# LED_Leg.net
KiCad netlist of a schematic drawn in EAGLE
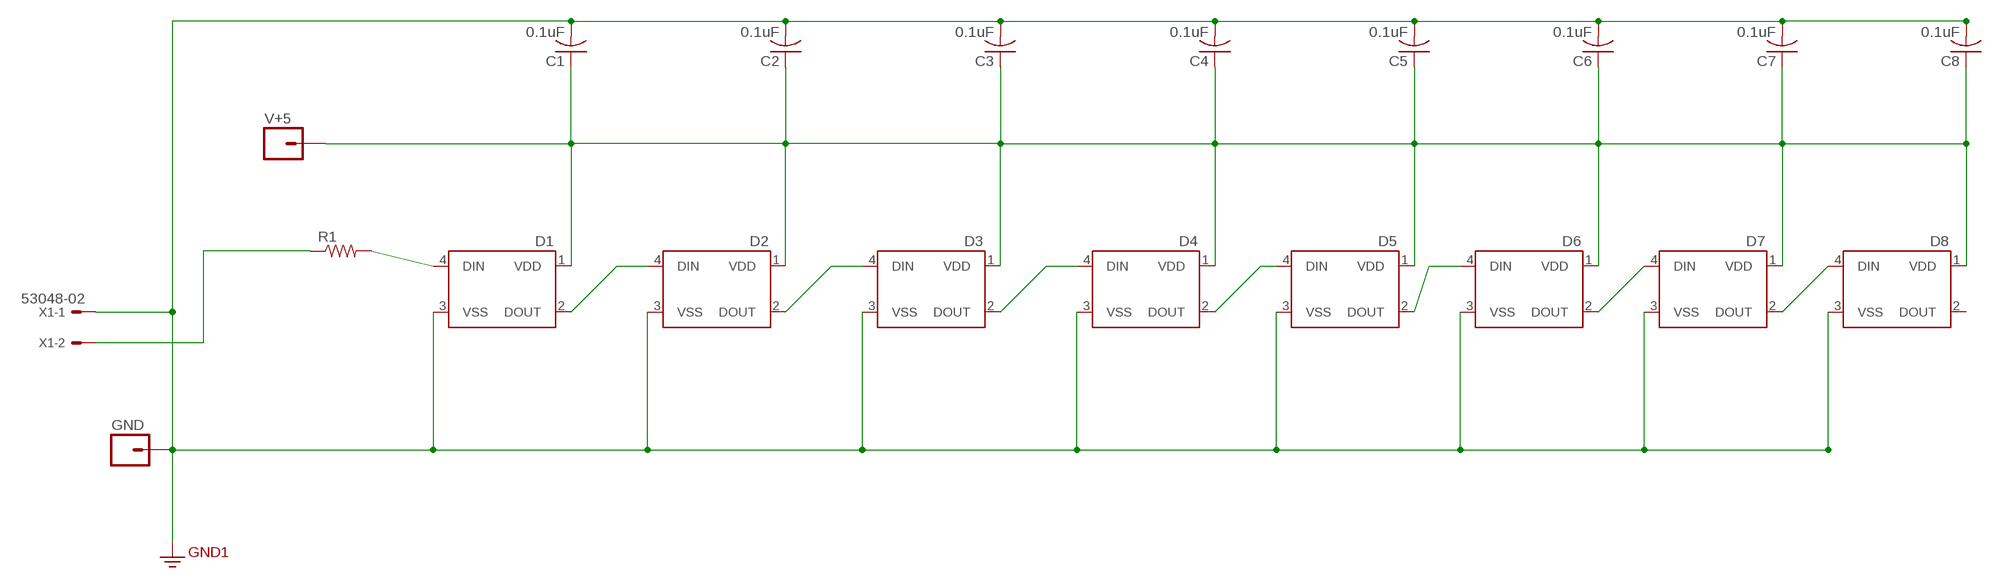
[diagram p0: schematic, sheet 1]

(export (version "E")
  (design (tool "Eeschema 10.0.6"))
  (components
    (comp (ref "C1")
      (value "0.1uF")
      (footprint "eagle-import:C0603K")
      (libsource (lib "eagle-import") (part "C-USC0603K"))
    )
    (comp (ref "C2")
      (value "0.1uF")
      (footprint "eagle-import:C0603K")
      (libsource (lib "eagle-import") (part "C-USC0603K"))
    )
    (comp (ref "C3")
      (value "0.1uF")
      (footprint "eagle-import:C0603K")
      (libsource (lib "eagle-import") (part "C-USC0603K"))
    )
    (comp (ref "C4")
      (value "0.1uF")
      (footprint "eagle-import:C0603K")
      (libsource (lib "eagle-import") (part "C-USC0603K"))
    )
    (comp (ref "C5")
      (value "0.1uF")
      (footprint "eagle-import:C0603K")
      (libsource (lib "eagle-import") (part "C-USC0603K"))
    )
    (comp (ref "C6")
      (value "0.1uF")
      (footprint "eagle-import:C0603K")
      (libsource (lib "eagle-import") (part "C-USC0603K"))
    )
    (comp (ref "C7")
      (value "0.1uF")
      (footprint "eagle-import:C0603K")
      (libsource (lib "eagle-import") (part "C-USC0603K"))
    )
    (comp (ref "C8")
      (value "0.1uF")
      (footprint "eagle-import:C0603K")
      (libsource (lib "eagle-import") (part "C-USC0603K"))
    )
    (comp (ref "D1")
      (value "WS2812B")
      (footprint "eagle-import:WS2812B")
      (libsource (lib "eagle-import") (part "WS2812B"))
    )
    (comp (ref "D2")
      (value "WS2812B")
      (footprint "eagle-import:WS2812B")
      (libsource (lib "eagle-import") (part "WS2812B"))
    )
    (comp (ref "D3")
      (value "WS2812B")
      (footprint "eagle-import:WS2812B")
      (libsource (lib "eagle-import") (part "WS2812B"))
    )
    (comp (ref "D4")
      (value "WS2812B")
      (footprint "eagle-import:WS2812B")
      (libsource (lib "eagle-import") (part "WS2812B"))
    )
    (comp (ref "D5")
      (value "WS2812B")
      (footprint "eagle-import:WS2812B")
      (libsource (lib "eagle-import") (part "WS2812B"))
    )
    (comp (ref "D6")
      (value "WS2812B")
      (footprint "eagle-import:WS2812B")
      (libsource (lib "eagle-import") (part "WS2812B"))
    )
    (comp (ref "D7")
      (value "WS2812B")
      (footprint "eagle-import:WS2812B")
      (libsource (lib "eagle-import") (part "WS2812B"))
    )
    (comp (ref "D8")
      (value "WS2812B")
      (footprint "eagle-import:WS2812B")
      (libsource (lib "eagle-import") (part "WS2812B"))
    )
    (comp (ref "GND")
      (value "M01NOSILK-KIT")
      (footprint "eagle-import:1X01NS-KIT")
      (libsource (lib "eagle-import") (part "M01NOSILK-KIT"))
    )
    (comp (ref "R1")
      (value "R-US_R0603")
      (footprint "eagle-import:R0603")
      (libsource (lib "eagle-import") (part "R-US_R0603"))
    )
    (comp (ref "V+5")
      (value "M01NOSILK-KIT")
      (footprint "eagle-import:1X01NS-KIT")
      (libsource (lib "eagle-import") (part "M01NOSILK-KIT"))
    )
    (comp (ref "X1")
      (value "53048-02")
      (footprint "eagle-import:53048-02")
      (fields (field (name "MF") "MOLEX") (field (name "MPN") "53048-0210"))
      (libsource (lib "eagle-import") (part "53?-02048"))
    )
  )
  (nets
    (net (code "1") (name "GND2") (class "Default")
      (node (ref "C1") (pin "2") (pinfunction "2_2") (pintype "passive"))
      (node (ref "C2") (pin "2") (pinfunction "2_2") (pintype "passive"))
      (node (ref "C3") (pin "2") (pinfunction "2_2") (pintype "passive"))
      (node (ref "C4") (pin "2") (pinfunction "2_2") (pintype "passive"))
      (node (ref "C5") (pin "2") (pinfunction "2_2") (pintype "passive"))
      (node (ref "C6") (pin "2") (pinfunction "2_2") (pintype "passive"))
      (node (ref "C7") (pin "2") (pinfunction "2_2") (pintype "passive"))
      (node (ref "C8") (pin "2") (pinfunction "2_2") (pintype "passive"))
      (node (ref "D1") (pin "3") (pinfunction "VSS_3") (pintype "power_in"))
      (node (ref "D2") (pin "3") (pinfunction "VSS_3") (pintype "power_in"))
      (node (ref "D3") (pin "3") (pinfunction "VSS_3") (pintype "power_in"))
      (node (ref "D4") (pin "3") (pinfunction "VSS_3") (pintype "power_in"))
      (node (ref "D5") (pin "3") (pinfunction "VSS_3") (pintype "power_in"))
      (node (ref "D6") (pin "3") (pinfunction "VSS_3") (pintype "power_in"))
      (node (ref "D7") (pin "3") (pinfunction "VSS_3") (pintype "power_in"))
      (node (ref "D8") (pin "3") (pinfunction "VSS_3") (pintype "power_in"))
      (node (ref "GND") (pin "1") (pinfunction "1_1") (pintype "passive"))
      (node (ref "X1") (pin "1") (pinfunction "S_1") (pintype "passive"))
    )
    (net (code "2") (name "Net-(D1-DIN)") (class "Default")
      (node (ref "D1") (pin "4") (pinfunction "DIN_4") (pintype "input"))
      (node (ref "R1") (pin "2") (pinfunction "2_2") (pintype "passive"))
    )
    (net (code "3") (name "Net-(D1-DOUT)") (class "Default")
      (node (ref "D1") (pin "2") (pinfunction "DOUT_2") (pintype "output"))
      (node (ref "D2") (pin "4") (pinfunction "DIN_4") (pintype "input"))
    )
    (net (code "4") (name "Net-(D1-VDD)") (class "Default")
      (node (ref "C1") (pin "1") (pinfunction "1_1") (pintype "passive"))
      (node (ref "C2") (pin "1") (pinfunction "1_1") (pintype "passive"))
      (node (ref "C3") (pin "1") (pinfunction "1_1") (pintype "passive"))
      (node (ref "C4") (pin "1") (pinfunction "1_1") (pintype "passive"))
      (node (ref "C5") (pin "1") (pinfunction "1_1") (pintype "passive"))
      (node (ref "C6") (pin "1") (pinfunction "1_1") (pintype "passive"))
      (node (ref "C7") (pin "1") (pinfunction "1_1") (pintype "passive"))
      (node (ref "C8") (pin "1") (pinfunction "1_1") (pintype "passive"))
      (node (ref "D1") (pin "1") (pinfunction "VDD_1") (pintype "power_in"))
      (node (ref "D2") (pin "1") (pinfunction "VDD_1") (pintype "power_in"))
      (node (ref "D3") (pin "1") (pinfunction "VDD_1") (pintype "power_in"))
      (node (ref "D4") (pin "1") (pinfunction "VDD_1") (pintype "power_in"))
      (node (ref "D5") (pin "1") (pinfunction "VDD_1") (pintype "power_in"))
      (node (ref "D6") (pin "1") (pinfunction "VDD_1") (pintype "power_in"))
      (node (ref "D7") (pin "1") (pinfunction "VDD_1") (pintype "power_in"))
      (node (ref "D8") (pin "1") (pinfunction "VDD_1") (pintype "power_in"))
      (node (ref "V+5") (pin "1") (pinfunction "1_1") (pintype "passive"))
    )
    (net (code "5") (name "Net-(D2-DOUT)") (class "Default")
      (node (ref "D2") (pin "2") (pinfunction "DOUT_2") (pintype "output"))
      (node (ref "D3") (pin "4") (pinfunction "DIN_4") (pintype "input"))
    )
    (net (code "6") (name "Net-(D3-DOUT)") (class "Default")
      (node (ref "D3") (pin "2") (pinfunction "DOUT_2") (pintype "output"))
      (node (ref "D4") (pin "4") (pinfunction "DIN_4") (pintype "input"))
    )
    (net (code "7") (name "Net-(D4-DOUT)") (class "Default")
      (node (ref "D4") (pin "2") (pinfunction "DOUT_2") (pintype "output"))
      (node (ref "D5") (pin "4") (pinfunction "DIN_4") (pintype "input"))
    )
    (net (code "8") (name "Net-(D5-DOUT)") (class "Default")
      (node (ref "D5") (pin "2") (pinfunction "DOUT_2") (pintype "output"))
      (node (ref "D6") (pin "4") (pinfunction "DIN_4") (pintype "input"))
    )
    (net (code "9") (name "Net-(D6-DOUT)") (class "Default")
      (node (ref "D6") (pin "2") (pinfunction "DOUT_2") (pintype "output"))
      (node (ref "D7") (pin "4") (pinfunction "DIN_4") (pintype "input"))
    )
    (net (code "10") (name "Net-(D7-DOUT)") (class "Default")
      (node (ref "D7") (pin "2") (pinfunction "DOUT_2") (pintype "output"))
      (node (ref "D8") (pin "4") (pinfunction "DIN_4") (pintype "input"))
    )
    (net (code "11") (name "Net-(X1B-S)") (class "Default")
      (node (ref "R1") (pin "1") (pinfunction "1_1") (pintype "passive"))
      (node (ref "X1") (pin "2") (pinfunction "S_2") (pintype "passive"))
    )
    (net (code "12") (name "unconnected-(D8-DOUT-Pad2)") (class "Default")
      (node (ref "D8") (pin "2") (pinfunction "DOUT_2") (pintype "output"))
    )
  )
)
